# T1_Schematic_RohanKumar_B24277.net
KiCad netlist of a schematic drawn in EasyEDA
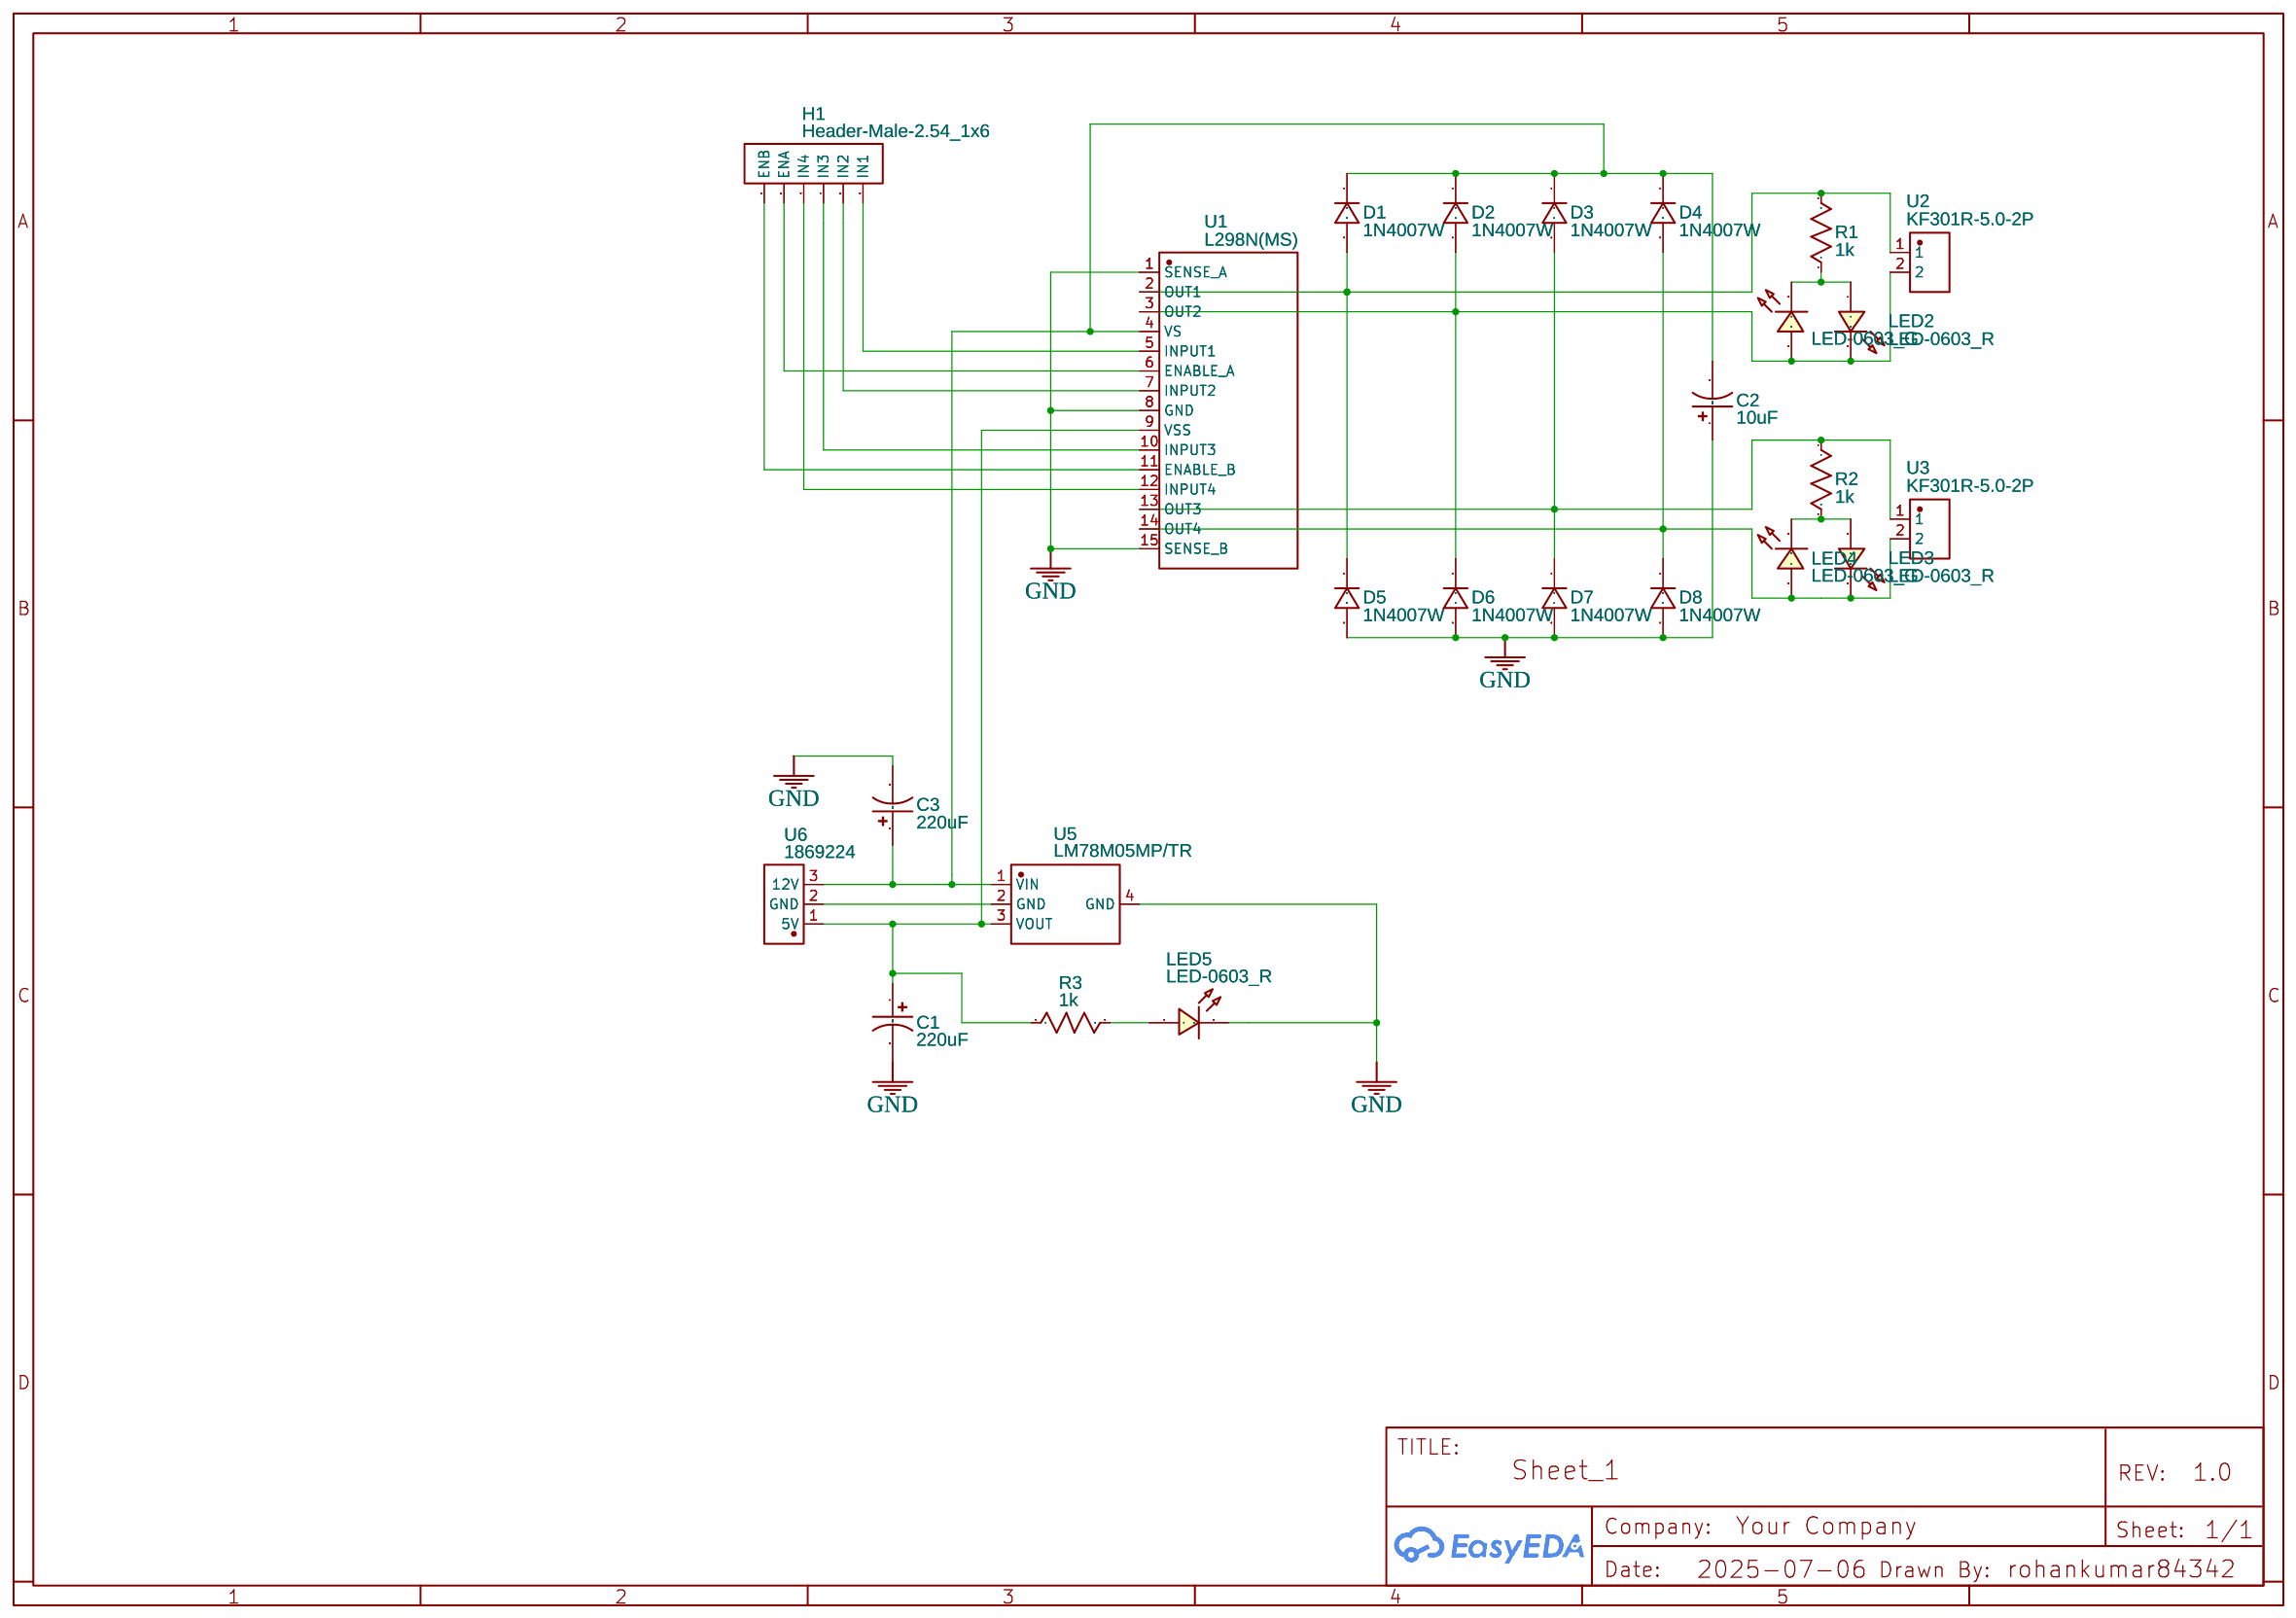
[diagram p0: schematic sheet]

(export (version "E")
  (design (tool "Eeschema 10.0.6"))
  (components
    (comp (ref "C1") (value "220uF") (libsource (lib "") (part "C_Tan_SMD_A_US")))
    (comp (ref "C2") (value "10uF") (libsource (lib "") (part "C_Tan_SMD_A_US_1")))
    (comp (ref "C3") (value "220uF") (libsource (lib "") (part "C_Tan_SMD_A_US_1")))
    (comp (ref "D1")
      (value "1N4007W")
      (fields (field (name "Manufacturer") "BLUE ROCKET"))
      (libsource (lib "") (part "1N4007W"))
    )
    (comp (ref "D2")
      (value "1N4007W")
      (fields (field (name "Manufacturer") "BLUE ROCKET"))
      (libsource (lib "") (part "1N4007W"))
    )
    (comp (ref "D3")
      (value "1N4007W")
      (fields (field (name "Manufacturer") "BLUE ROCKET"))
      (libsource (lib "") (part "1N4007W"))
    )
    (comp (ref "D4")
      (value "1N4007W")
      (fields (field (name "Manufacturer") "BLUE ROCKET"))
      (libsource (lib "") (part "1N4007W"))
    )
    (comp (ref "D5")
      (value "1N4007W")
      (fields (field (name "Manufacturer") "BLUE ROCKET"))
      (libsource (lib "") (part "1N4007W"))
    )
    (comp (ref "D6")
      (value "1N4007W")
      (fields (field (name "Manufacturer") "BLUE ROCKET"))
      (libsource (lib "") (part "1N4007W"))
    )
    (comp (ref "D7")
      (value "1N4007W")
      (fields (field (name "Manufacturer") "BLUE ROCKET"))
      (libsource (lib "") (part "1N4007W"))
    )
    (comp (ref "D8")
      (value "1N4007W")
      (fields (field (name "Manufacturer") "BLUE ROCKET"))
      (libsource (lib "") (part "1N4007W"))
    )
    (comp (ref "H1")
      (value "Header-Male-2.54_1x6")
      (fields (field (name "Manufacturer Part") "2.54-1x6P直针") (field (name "Manufacturer") "BOOMELE(博穆精密)"))
      (libsource (lib "") (part "Header-Male-2.54_1x6"))
    )
    (comp (ref "LED1")
      (value "LED-0603_G")
      (fields
        (field (name "Manufacturer Part") "19-217/GHC-YR1S2/3T")
        (field (name "Manufacturer") "EVERLIGHT(台湾亿光)")
      )
      (libsource (lib "") (part "LED-0603_G"))
    )
    (comp (ref "LED2")
      (value "LED-0603_R")
      (fields
        (field (name "Manufacturer Part") "19-217/R6C-AL1M2VY/3T")
        (field (name "Manufacturer") "EVERLIGHT(台湾亿光)")
      )
      (libsource (lib "") (part "LED-0603_R_1"))
    )
    (comp (ref "LED3")
      (value "LED-0603_R")
      (fields
        (field (name "Manufacturer Part") "19-217/R6C-AL1M2VY/3T")
        (field (name "Manufacturer") "EVERLIGHT(台湾亿光)")
      )
      (libsource (lib "") (part "LED-0603_R_1"))
    )
    (comp (ref "LED4")
      (value "LED-0603_G")
      (fields
        (field (name "Manufacturer Part") "19-217/GHC-YR1S2/3T")
        (field (name "Manufacturer") "EVERLIGHT(台湾亿光)")
      )
      (libsource (lib "") (part "LED-0603_G"))
    )
    (comp (ref "LED5")
      (value "LED-0603_R")
      (fields
        (field (name "Manufacturer Part") "19-217/R6C-AL1M2VY/3T")
        (field (name "Manufacturer") "EVERLIGHT(台湾亿光)")
      )
      (libsource (lib "") (part "LED-0603_R"))
    )
    (comp (ref "R1") (value "1k") (libsource (lib "") (part "R_0603_US_1")))
    (comp (ref "R2") (value "1k") (libsource (lib "") (part "R_0603_US_2")))
    (comp (ref "R3") (value "1k") (libsource (lib "") (part "R_0603_US")))
    (comp (ref "U1")
      (value "L298N(MS)")
      (fields (field (name "Manufacturer") "MSKSEMI(美森科)"))
      (libsource (lib "") (part "L298N(MS)"))
    )
    (comp (ref "U2")
      (value "KF301R-5.0-2P")
      (fields (field (name "Manufacturer") "KEFA(科发)"))
      (libsource (lib "") (part "KF301R-5.0-2P"))
    )
    (comp (ref "U3")
      (value "KF301R-5.0-2P")
      (fields (field (name "Manufacturer") "KEFA(科发)"))
      (libsource (lib "") (part "KF301R-5.0-2P"))
    )
    (comp (ref "U5")
      (value "LM78M05MP/TR")
      (fields (field (name "Manufacturer") "HGSEMI(华冠)"))
      (libsource (lib "") (part "LM78M05MP/TR"))
    )
    (comp (ref "U6")
      (value "1869224")
      (fields (field (name "Manufacturer") "Phoenix Contact(菲尼克斯)"))
      (libsource (lib "") (part "1869224"))
    )
  )
  (nets
    (net (code "1") (name "GND") (class "Default")
      (node (ref "C1") (pin "2") (pinfunction "2_2") (pintype "unspecified"))
      (node (ref "C2") (pin "1") (pinfunction "1_1") (pintype "unspecified"))
      (node (ref "C3") (pin "2") (pinfunction "2_2") (pintype "unspecified"))
      (node (ref "D5") (pin "2") (pinfunction "2_2") (pintype "unspecified"))
      (node (ref "D6") (pin "2") (pinfunction "2_2") (pintype "unspecified"))
      (node (ref "D7") (pin "2") (pinfunction "2_2") (pintype "unspecified"))
      (node (ref "D8") (pin "2") (pinfunction "2_2") (pintype "unspecified"))
      (node (ref "LED5") (pin "2") (pinfunction "2_2") (pintype "unspecified"))
      (node (ref "U1") (pin "1") (pinfunction "SENSE_A_1") (pintype "unspecified"))
      (node (ref "U1") (pin "15") (pinfunction "SENSE_B_15") (pintype "unspecified"))
      (node (ref "U1") (pin "8") (pinfunction "GND_8") (pintype "unspecified"))
      (node (ref "U5") (pin "4") (pinfunction "GND_4") (pintype "unspecified"))
    )
    (net (code "2") (name "Net-(H1-ENA)") (class "Default")
      (node (ref "H1") (pin "2") (pinfunction "ENA_2") (pintype "input"))
      (node (ref "U1") (pin "6") (pinfunction "ENABLE_A_6") (pintype "unspecified"))
    )
    (net (code "3") (name "Net-(H1-ENB)") (class "Default")
      (node (ref "H1") (pin "1") (pinfunction "ENB_1") (pintype "input"))
      (node (ref "U1") (pin "11") (pinfunction "ENABLE_B_11") (pintype "unspecified"))
    )
    (net (code "4") (name "Net-(H1-IN1)") (class "Default")
      (node (ref "H1") (pin "6") (pinfunction "IN1_6") (pintype "input"))
      (node (ref "U1") (pin "5") (pinfunction "INPUT1_5") (pintype "unspecified"))
    )
    (net (code "5") (name "Net-(H1-IN2)") (class "Default")
      (node (ref "H1") (pin "5") (pinfunction "IN2_5") (pintype "input"))
      (node (ref "U1") (pin "7") (pinfunction "INPUT2_7") (pintype "unspecified"))
    )
    (net (code "6") (name "Net-(H1-IN3)") (class "Default")
      (node (ref "H1") (pin "4") (pinfunction "IN3_4") (pintype "input"))
      (node (ref "U1") (pin "10") (pinfunction "INPUT3_10") (pintype "unspecified"))
    )
    (net (code "7") (name "Net-(H1-IN4)") (class "Default")
      (node (ref "H1") (pin "3") (pinfunction "IN4_3") (pintype "input"))
      (node (ref "U1") (pin "12") (pinfunction "INPUT4_12") (pintype "unspecified"))
    )
    (net (code "8") (name "Net-(LED1-Pad2)") (class "Default")
      (node (ref "LED1") (pin "2") (pinfunction "2_2") (pintype "unspecified"))
      (node (ref "LED2") (pin "1") (pinfunction "1_1") (pintype "unspecified"))
      (node (ref "R1") (pin "1") (pinfunction "1_1") (pintype "unspecified"))
    )
    (net (code "9") (name "Net-(LED3-Pad1)") (class "Default")
      (node (ref "LED3") (pin "1") (pinfunction "1_1") (pintype "unspecified"))
      (node (ref "LED4") (pin "2") (pinfunction "2_2") (pintype "unspecified"))
      (node (ref "R2") (pin "2") (pinfunction "2_2") (pintype "unspecified"))
    )
    (net (code "10") (name "Net-(LED5-Pad1)") (class "Default")
      (node (ref "LED5") (pin "1") (pinfunction "1_1") (pintype "unspecified"))
      (node (ref "R3") (pin "2") (pinfunction "2_2") (pintype "unspecified"))
    )
    (net (code "11") (name "Net-(U1-OUT1)") (class "Default")
      (node (ref "D1") (pin "2") (pinfunction "2_2") (pintype "unspecified"))
      (node (ref "D5") (pin "1") (pinfunction "1_1") (pintype "unspecified"))
      (node (ref "R1") (pin "2") (pinfunction "2_2") (pintype "unspecified"))
      (node (ref "U1") (pin "2") (pinfunction "OUT1_2") (pintype "unspecified"))
      (node (ref "U2") (pin "1") (pinfunction "1_1") (pintype "unspecified"))
    )
    (net (code "12") (name "Net-(U1-OUT2)") (class "Default")
      (node (ref "D2") (pin "2") (pinfunction "2_2") (pintype "unspecified"))
      (node (ref "D6") (pin "1") (pinfunction "1_1") (pintype "unspecified"))
      (node (ref "LED1") (pin "1") (pinfunction "1_1") (pintype "unspecified"))
      (node (ref "LED2") (pin "2") (pinfunction "2_2") (pintype "unspecified"))
      (node (ref "U1") (pin "3") (pinfunction "OUT2_3") (pintype "unspecified"))
      (node (ref "U2") (pin "2") (pinfunction "2_2") (pintype "unspecified"))
    )
    (net (code "13") (name "Net-(U1-OUT3)") (class "Default")
      (node (ref "D3") (pin "2") (pinfunction "2_2") (pintype "unspecified"))
      (node (ref "D7") (pin "1") (pinfunction "1_1") (pintype "unspecified"))
      (node (ref "R2") (pin "1") (pinfunction "1_1") (pintype "unspecified"))
      (node (ref "U1") (pin "13") (pinfunction "OUT3_13") (pintype "unspecified"))
      (node (ref "U3") (pin "1") (pinfunction "1_1") (pintype "unspecified"))
    )
    (net (code "14") (name "Net-(U1-OUT4)") (class "Default")
      (node (ref "D4") (pin "2") (pinfunction "2_2") (pintype "unspecified"))
      (node (ref "D8") (pin "1") (pinfunction "1_1") (pintype "unspecified"))
      (node (ref "LED3") (pin "2") (pinfunction "2_2") (pintype "unspecified"))
      (node (ref "LED4") (pin "1") (pinfunction "1_1") (pintype "unspecified"))
      (node (ref "U1") (pin "14") (pinfunction "OUT4_14") (pintype "unspecified"))
      (node (ref "U3") (pin "2") (pinfunction "2_2") (pintype "unspecified"))
    )
    (net (code "15") (name "Net-(U1-VS)") (class "Default")
      (node (ref "C2") (pin "2") (pinfunction "2_2") (pintype "unspecified"))
      (node (ref "C3") (pin "1") (pinfunction "1_1") (pintype "unspecified"))
      (node (ref "D1") (pin "1") (pinfunction "1_1") (pintype "unspecified"))
      (node (ref "D2") (pin "1") (pinfunction "1_1") (pintype "unspecified"))
      (node (ref "D3") (pin "1") (pinfunction "1_1") (pintype "unspecified"))
      (node (ref "D4") (pin "1") (pinfunction "1_1") (pintype "unspecified"))
      (node (ref "U1") (pin "4") (pinfunction "VS_4") (pintype "unspecified"))
      (node (ref "U5") (pin "1") (pinfunction "VIN_1") (pintype "unspecified"))
      (node (ref "U6") (pin "3") (pinfunction "12V_3") (pintype "unspecified"))
    )
    (net (code "16") (name "Net-(U1-VSS)") (class "Default")
      (node (ref "C1") (pin "1") (pinfunction "1_1") (pintype "unspecified"))
      (node (ref "R3") (pin "1") (pinfunction "1_1") (pintype "unspecified"))
      (node (ref "U1") (pin "9") (pinfunction "VSS_9") (pintype "unspecified"))
      (node (ref "U5") (pin "3") (pinfunction "VOUT_3") (pintype "unspecified"))
      (node (ref "U6") (pin "1") (pinfunction "5V_1") (pintype "unspecified"))
    )
    (net (code "17") (name "Net-(U6-GND)") (class "Default")
      (node (ref "U5") (pin "2") (pinfunction "GND_2") (pintype "unspecified"))
      (node (ref "U6") (pin "2") (pinfunction "GND_2") (pintype "unspecified"))
    )
  )
)
